# kapal2.net
KiCad netlist of a schematic drawn in EAGLE
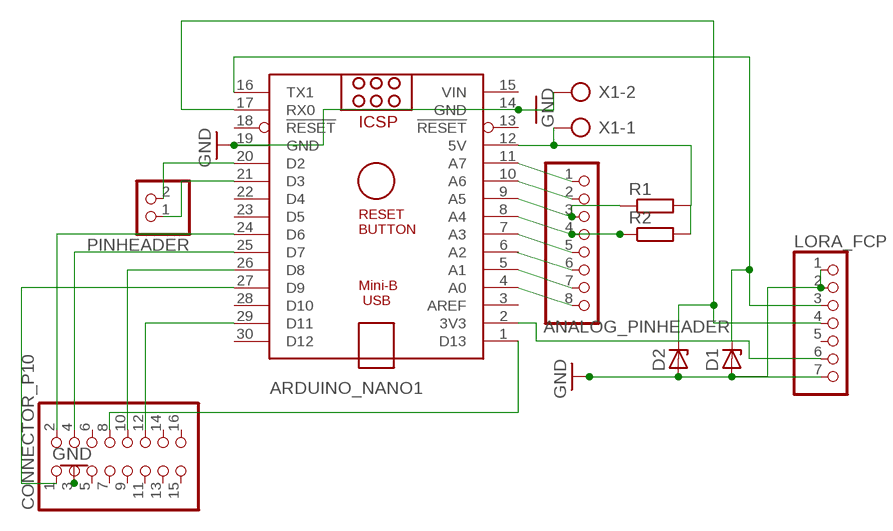
[diagram p0: schematic, sheet 1]

(export (version "E")
  (design (tool "Eeschema 10.0.6"))
  (components
    (comp (ref "ANALOG_PINHEADER")
      (value "PINHD-1X8")
      (footprint "eagle-import:1X08")
      (libsource (lib "eagle-import") (part "PINHD-1X8"))
    )
    (comp (ref "ARDUINO_NANO1")
      (value "ARDUINO_NANO")
      (footprint "eagle-import:ARDUINO_NANO")
      (libsource (lib "eagle-import") (part "ARDUINO_NANO"))
    )
    (comp (ref "CONNECTOR_P10")
      (value "PINHD-2X8")
      (footprint "eagle-import:2X08")
      (libsource (lib "eagle-import") (part "PINHD-2X8"))
    )
    (comp (ref "D1")
      (value "ZENER-DIODEDO35Z10")
      (footprint "eagle-import:DO35Z10")
      (libsource (lib "eagle-import") (part "ZENER-DIODEDO35Z10"))
    )
    (comp (ref "D2")
      (value "ZENER-DIODEDO35Z10")
      (footprint "eagle-import:DO35Z10")
      (libsource (lib "eagle-import") (part "ZENER-DIODEDO35Z10"))
    )
    (comp (ref "LORA_FCP")
      (value "PINHD-1X7")
      (footprint "eagle-import:1X07")
      (libsource (lib "eagle-import") (part "PINHD-1X7"))
    )
    (comp (ref "PINHEADER")
      (value "PINHD-1X2")
      (footprint "eagle-import:1X02")
      (libsource (lib "eagle-import") (part "PINHD-1X2"))
    )
    (comp (ref "R1")
      (value "R-EU_0204/7")
      (footprint "eagle-import:0204_7")
      (libsource (lib "eagle-import") (part "R-EU_0204/7"))
    )
    (comp (ref "R2")
      (value "R-EU_0204/7")
      (footprint "eagle-import:0204_7")
      (libsource (lib "eagle-import") (part "R-EU_0204/7"))
    )
    (comp (ref "X1")
      (value "AK300/2")
      (footprint "eagle-import:AK300_2")
      (libsource (lib "eagle-import") (part "AK300/2"))
    )
  )
  (nets
    (net (code "1") (name "/VIN") (class "Default")
      (node (ref "ARDUINO_NANO1") (pin "15") (pinfunction "VIN_15") (pintype "power_in"))
    )
    (net (code "2") (name "GND") (class "Default")
      (node (ref "ARDUINO_NANO1") (pin "14") (pinfunction "GND_14") (pintype "power_in"))
      (node (ref "ARDUINO_NANO1") (pin "19") (pinfunction "GND_19") (pintype "power_in"))
      (node (ref "CONNECTOR_P10") (pin "3") (pinfunction "3_3") (pintype "passive"))
      (node (ref "D1") (pin "A") (pinfunction "A_A") (pintype "passive"))
      (node (ref "D2") (pin "A") (pinfunction "A_A") (pintype "passive"))
      (node (ref "LORA_FCP") (pin "1") (pinfunction "1_1") (pintype "passive"))
      (node (ref "LORA_FCP") (pin "2") (pinfunction "2_2") (pintype "passive"))
      (node (ref "LORA_FCP") (pin "7") (pinfunction "7_7") (pintype "passive"))
      (node (ref "X1") (pin "2") (pinfunction "KL_2") (pintype "passive"))
    )
    (net (code "3") (name "Net-(ARDUINO_NANO1-3V3)") (class "Default")
      (node (ref "ARDUINO_NANO1") (pin "2") (pinfunction "3V3_2") (pintype "output"))
      (node (ref "LORA_FCP") (pin "6") (pinfunction "6_6") (pintype "passive"))
    )
    (net (code "4") (name "Net-(ARDUINO_NANO1-5V)") (class "Default")
      (node (ref "ARDUINO_NANO1") (pin "12") (pinfunction "5V_12") (pintype "power_in"))
      (node (ref "R1") (pin "2") (pinfunction "2_2") (pintype "passive"))
      (node (ref "R2") (pin "2") (pinfunction "2_2") (pintype "passive"))
      (node (ref "X1") (pin "1") (pinfunction "KL_1") (pintype "passive"))
    )
    (net (code "5") (name "Net-(ARDUINO_NANO1-A0)") (class "Default")
      (node (ref "ANALOG_PINHEADER") (pin "8") (pinfunction "8_8") (pintype "passive"))
      (node (ref "ARDUINO_NANO1") (pin "4") (pinfunction "A0_4") (pintype "bidirectional"))
    )
    (net (code "6") (name "Net-(ARDUINO_NANO1-A1)") (class "Default")
      (node (ref "ANALOG_PINHEADER") (pin "7") (pinfunction "7_7") (pintype "passive"))
      (node (ref "ARDUINO_NANO1") (pin "5") (pinfunction "A1_5") (pintype "bidirectional"))
    )
    (net (code "7") (name "Net-(ARDUINO_NANO1-A3)") (class "Default")
      (node (ref "ANALOG_PINHEADER") (pin "5") (pinfunction "5_5") (pintype "passive"))
      (node (ref "ARDUINO_NANO1") (pin "7") (pinfunction "A3_7") (pintype "bidirectional"))
    )
    (net (code "8") (name "Net-(ARDUINO_NANO1-A4)") (class "Default")
      (node (ref "ANALOG_PINHEADER") (pin "4") (pinfunction "4_4") (pintype "passive"))
      (node (ref "ARDUINO_NANO1") (pin "8") (pinfunction "A4_8") (pintype "bidirectional"))
      (node (ref "R2") (pin "1") (pinfunction "1_1") (pintype "passive"))
    )
    (net (code "9") (name "Net-(ARDUINO_NANO1-A5)") (class "Default")
      (node (ref "ANALOG_PINHEADER") (pin "3") (pinfunction "3_3") (pintype "passive"))
      (node (ref "ARDUINO_NANO1") (pin "9") (pinfunction "A5_9") (pintype "bidirectional"))
      (node (ref "R1") (pin "1") (pinfunction "1_1") (pintype "passive"))
    )
    (net (code "10") (name "Net-(ARDUINO_NANO1-A6)") (class "Default")
      (node (ref "ANALOG_PINHEADER") (pin "2") (pinfunction "2_2") (pintype "passive"))
      (node (ref "ARDUINO_NANO1") (pin "10") (pinfunction "A6_10") (pintype "bidirectional"))
    )
    (net (code "11") (name "Net-(ARDUINO_NANO1-A7)") (class "Default")
      (node (ref "ANALOG_PINHEADER") (pin "1") (pinfunction "1_1") (pintype "passive"))
      (node (ref "ARDUINO_NANO1") (pin "11") (pinfunction "A7_11") (pintype "bidirectional"))
    )
    (net (code "12") (name "Net-(ARDUINO_NANO1-D2)") (class "Default")
      (node (ref "ARDUINO_NANO1") (pin "20") (pinfunction "D2_20") (pintype "bidirectional"))
      (node (ref "PINHEADER") (pin "2") (pinfunction "2_2") (pintype "passive"))
    )
    (net (code "13") (name "Net-(ARDUINO_NANO1-D3)") (class "Default")
      (node (ref "ARDUINO_NANO1") (pin "21") (pinfunction "D3_21") (pintype "bidirectional"))
      (node (ref "PINHEADER") (pin "1") (pinfunction "1_1") (pintype "passive"))
    )
    (net (code "14") (name "Net-(ARDUINO_NANO1-D6)") (class "Default")
      (node (ref "ARDUINO_NANO1") (pin "24") (pinfunction "D6_24") (pintype "bidirectional"))
      (node (ref "CONNECTOR_P10") (pin "2") (pinfunction "2_2") (pintype "passive"))
    )
    (net (code "15") (name "Net-(ARDUINO_NANO1-D7)") (class "Default")
      (node (ref "ARDUINO_NANO1") (pin "25") (pinfunction "D7_25") (pintype "bidirectional"))
      (node (ref "CONNECTOR_P10") (pin "4") (pinfunction "4_4") (pintype "passive"))
    )
    (net (code "16") (name "Net-(ARDUINO_NANO1-D8)") (class "Default")
      (node (ref "ARDUINO_NANO1") (pin "26") (pinfunction "D8_26") (pintype "bidirectional"))
      (node (ref "CONNECTOR_P10") (pin "10") (pinfunction "10_10") (pintype "passive"))
    )
    (net (code "17") (name "Net-(ARDUINO_NANO1-D9)") (class "Default")
      (node (ref "ARDUINO_NANO1") (pin "27") (pinfunction "D9_27") (pintype "bidirectional"))
      (node (ref "CONNECTOR_P10") (pin "1") (pinfunction "1_1") (pintype "passive"))
    )
    (net (code "18") (name "Net-(ARDUINO_NANO1-D11)") (class "Default")
      (node (ref "ARDUINO_NANO1") (pin "29") (pinfunction "D11_29") (pintype "bidirectional"))
      (node (ref "CONNECTOR_P10") (pin "12") (pinfunction "12_12") (pintype "passive"))
    )
    (net (code "19") (name "Net-(ARDUINO_NANO1-D13)") (class "Default")
      (node (ref "ARDUINO_NANO1") (pin "1") (pinfunction "D13_1") (pintype "bidirectional"))
      (node (ref "CONNECTOR_P10") (pin "8") (pinfunction "8_8") (pintype "passive"))
    )
    (net (code "20") (name "Net-(ARDUINO_NANO1-RX0)") (class "Default")
      (node (ref "ARDUINO_NANO1") (pin "17") (pinfunction "RX0_17") (pintype "bidirectional"))
      (node (ref "D2") (pin "C") (pinfunction "C_C") (pintype "passive"))
      (node (ref "LORA_FCP") (pin "4") (pinfunction "4_4") (pintype "passive"))
    )
    (net (code "21") (name "Net-(ARDUINO_NANO1-TX1)") (class "Default")
      (node (ref "ARDUINO_NANO1") (pin "16") (pinfunction "TX1_16") (pintype "bidirectional"))
      (node (ref "D1") (pin "C") (pinfunction "C_C") (pintype "passive"))
      (node (ref "LORA_FCP") (pin "3") (pinfunction "3_3") (pintype "passive"))
    )
    (net (code "22") (name "unconnected-(ANALOG_PINHEADER-Pad6)") (class "Default")
      (node (ref "ANALOG_PINHEADER") (pin "6") (pinfunction "6_6") (pintype "passive"))
    )
    (net (code "23") (name "unconnected-(ARDUINO_NANO1-A2-Pad6)") (class "Default")
      (node (ref "ARDUINO_NANO1") (pin "6") (pinfunction "A2_6") (pintype "bidirectional"))
    )
    (net (code "24") (name "unconnected-(ARDUINO_NANO1-AREF-Pad3)") (class "Default")
      (node (ref "ARDUINO_NANO1") (pin "3") (pinfunction "AREF_3") (pintype "input"))
    )
    (net (code "25") (name "unconnected-(ARDUINO_NANO1-D4-Pad22)") (class "Default")
      (node (ref "ARDUINO_NANO1") (pin "22") (pinfunction "D4_22") (pintype "bidirectional"))
    )
    (net (code "26") (name "unconnected-(ARDUINO_NANO1-D5-Pad23)") (class "Default")
      (node (ref "ARDUINO_NANO1") (pin "23") (pinfunction "D5_23") (pintype "bidirectional"))
    )
    (net (code "27") (name "unconnected-(ARDUINO_NANO1-D10-Pad28)") (class "Default")
      (node (ref "ARDUINO_NANO1") (pin "28") (pinfunction "D10_28") (pintype "bidirectional"))
    )
    (net (code "28") (name "unconnected-(ARDUINO_NANO1-D12-Pad30)") (class "Default")
      (node (ref "ARDUINO_NANO1") (pin "30") (pinfunction "D12_30") (pintype "bidirectional"))
    )
    (net (code "29") (name "unconnected-(ARDUINO_NANO1-~{RESET}-Pad13)") (class "Default")
      (node (ref "ARDUINO_NANO1") (pin "13") (pinfunction "~{RESET}_13") (pintype "input"))
    )
    (net (code "30") (name "unconnected-(ARDUINO_NANO1-~{RESET}-Pad18)") (class "Default")
      (node (ref "ARDUINO_NANO1") (pin "18") (pinfunction "~{RESET}_18") (pintype "input"))
    )
    (net (code "31") (name "unconnected-(CONNECTOR_P10-Pad5)") (class "Default")
      (node (ref "CONNECTOR_P10") (pin "5") (pinfunction "5_5") (pintype "passive"))
    )
    (net (code "32") (name "unconnected-(CONNECTOR_P10-Pad6)") (class "Default")
      (node (ref "CONNECTOR_P10") (pin "6") (pinfunction "6_6") (pintype "passive"))
    )
    (net (code "33") (name "unconnected-(CONNECTOR_P10-Pad7)") (class "Default")
      (node (ref "CONNECTOR_P10") (pin "7") (pinfunction "7_7") (pintype "passive"))
    )
    (net (code "34") (name "unconnected-(CONNECTOR_P10-Pad9)") (class "Default")
      (node (ref "CONNECTOR_P10") (pin "9") (pinfunction "9_9") (pintype "passive"))
    )
    (net (code "35") (name "unconnected-(CONNECTOR_P10-Pad11)") (class "Default")
      (node (ref "CONNECTOR_P10") (pin "11") (pinfunction "11_11") (pintype "passive"))
    )
    (net (code "36") (name "unconnected-(CONNECTOR_P10-Pad13)") (class "Default")
      (node (ref "CONNECTOR_P10") (pin "13") (pinfunction "13_13") (pintype "passive"))
    )
    (net (code "37") (name "unconnected-(CONNECTOR_P10-Pad14)") (class "Default")
      (node (ref "CONNECTOR_P10") (pin "14") (pinfunction "14_14") (pintype "passive"))
    )
    (net (code "38") (name "unconnected-(CONNECTOR_P10-Pad15)") (class "Default")
      (node (ref "CONNECTOR_P10") (pin "15") (pinfunction "15_15") (pintype "passive"))
    )
    (net (code "39") (name "unconnected-(CONNECTOR_P10-Pad16)") (class "Default")
      (node (ref "CONNECTOR_P10") (pin "16") (pinfunction "16_16") (pintype "passive"))
    )
    (net (code "40") (name "unconnected-(LORA_FCP-Pad5)") (class "Default")
      (node (ref "LORA_FCP") (pin "5") (pinfunction "5_5") (pintype "passive"))
    )
  )
)
